# Motor-Driver.net
KiCad netlist of a schematic drawn in EAGLE
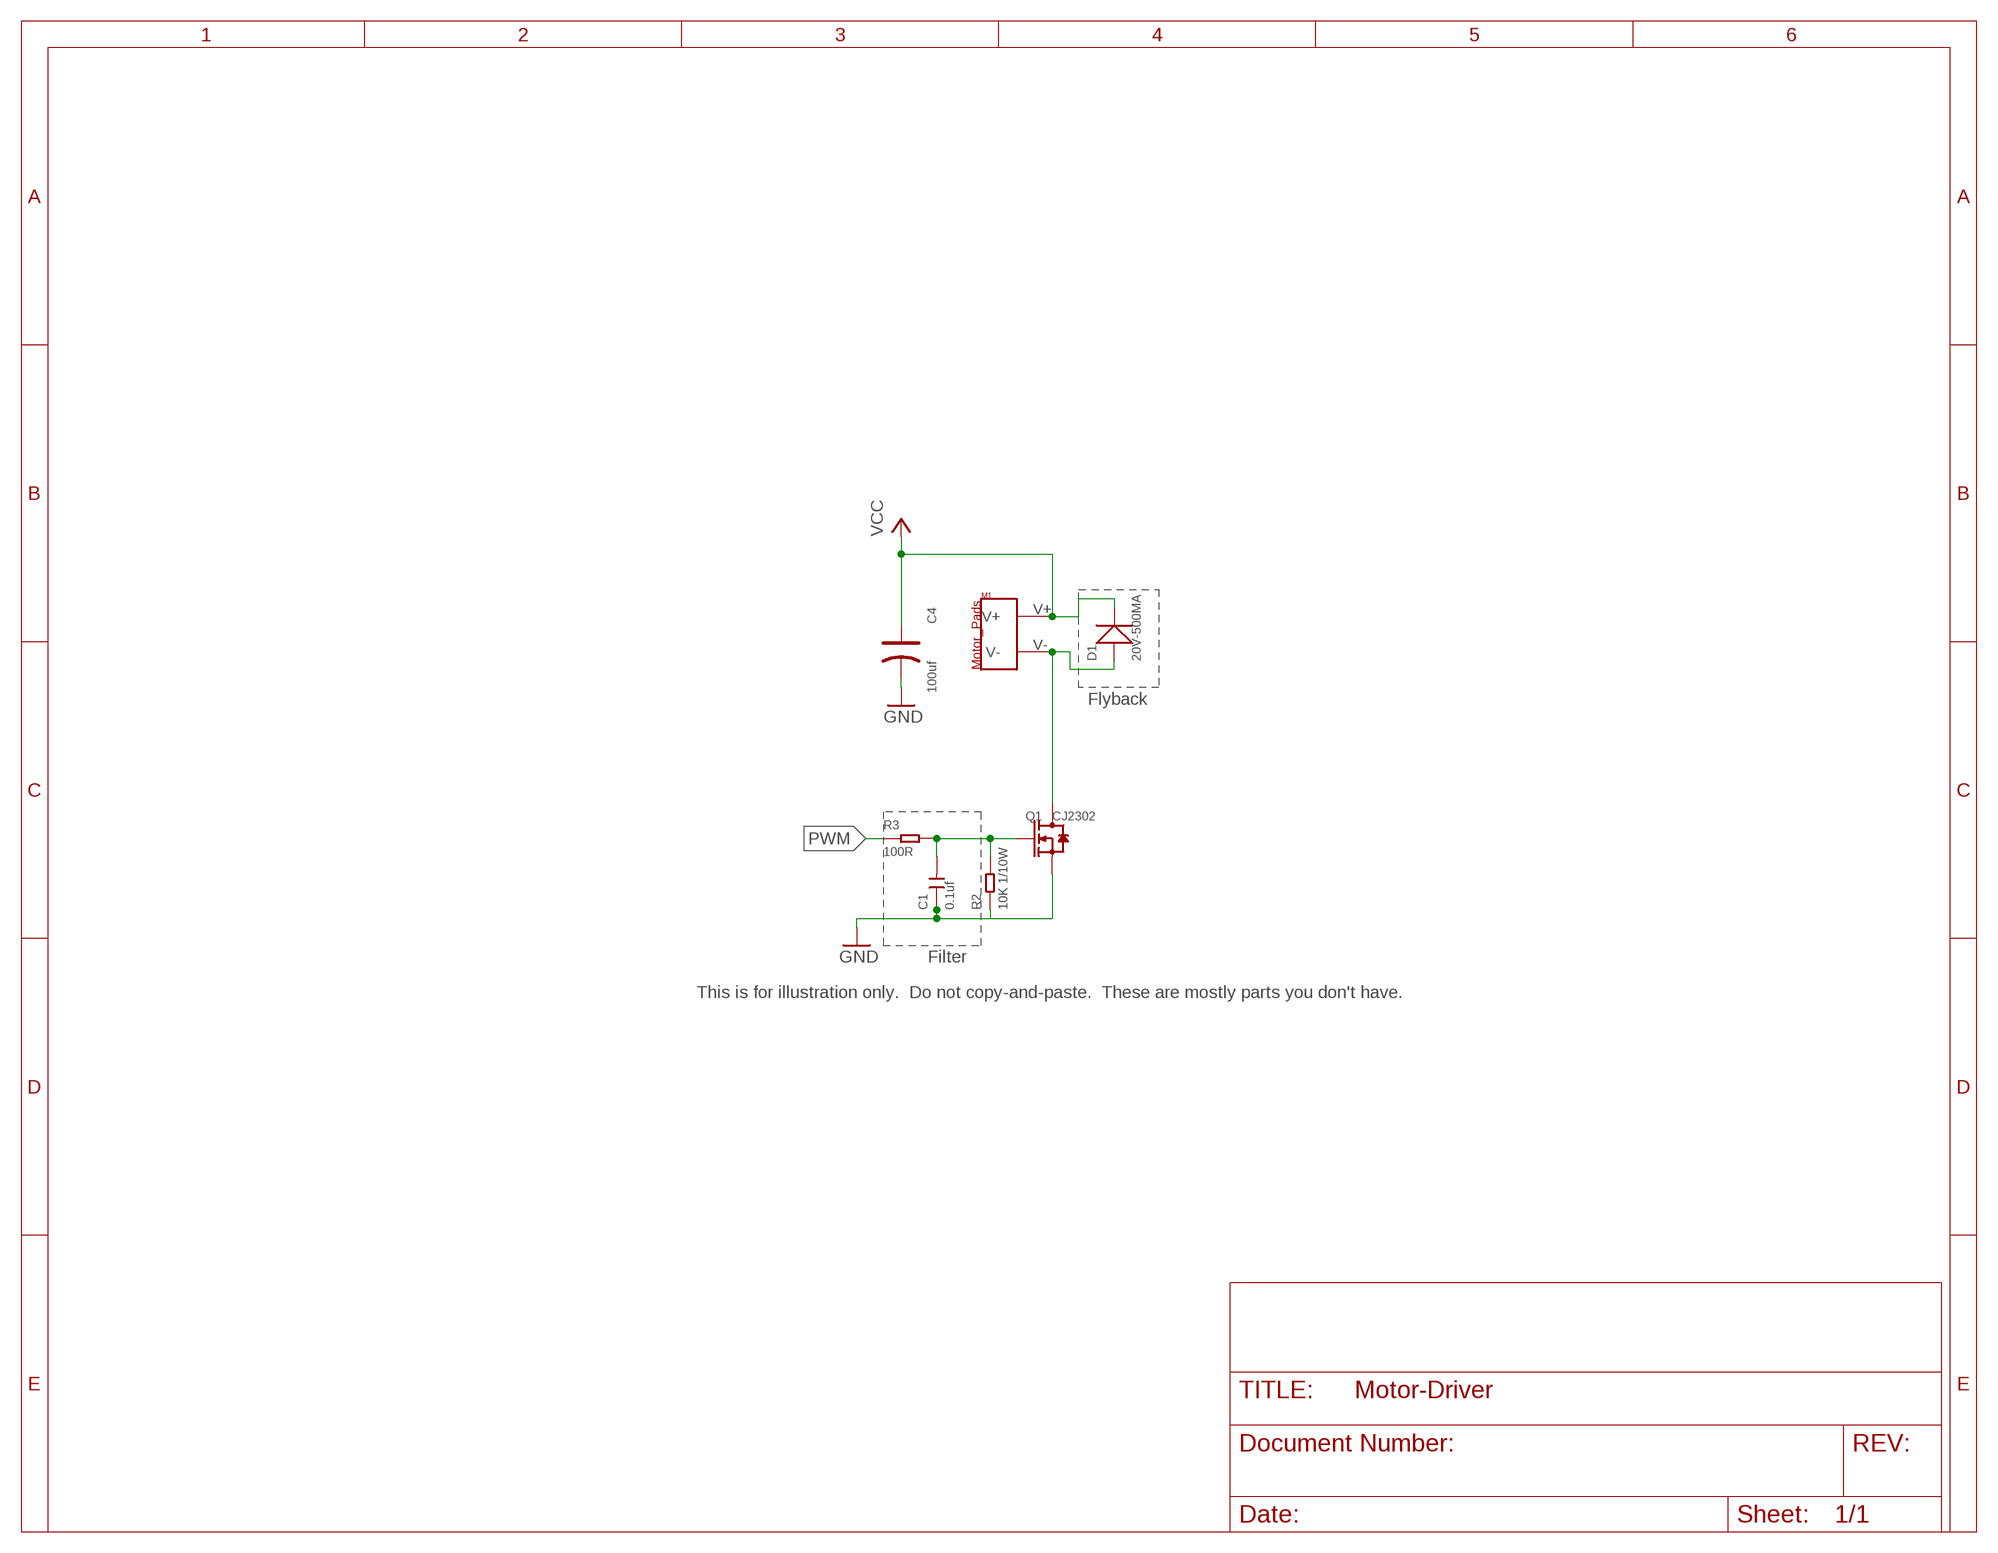
[diagram p0: schematic, sheet 1]

(export (version "E")
  (design (tool "Eeschema 10.0.6"))
  (components
    (comp (ref "C1")
      (value "0.1uf")
      (footprint "eagle-import:C0402")
      (fields (field (name "MPN") "CC0402KRX5R6BB105"))
      (libsource (lib "eagle-import") (part "CERAMIC-1UF-10V-10%-X5R(0402)"))
    )
    (comp (ref "C4")
      (value "100uf")
      (footprint "eagle-import:AVX-B")
      (fields (field (name "MPN") "TAJB107M010#NJ"))
      (libsource (lib "eagle-import") (part "TANTALUM-SMD-100UF-10V(AVX-B)"))
    )
    (comp (ref "D1")
      (value "20V-500MA")
      (footprint "eagle-import:SOD-123")
      (fields (field (name "MPN") "SS0520-7-F"))
      (libsource (lib "eagle-import") (part "SMD-DIODE-SCHOTTKY-20V-500MA(SOD-123)"))
    )
    (comp (ref "M1")
      (value "MOTOR_PADS")
      (footprint "eagle-import:MOTOR_PADS")
      (libsource (lib "eagle-import") (part "MOTOR_PADS"))
    )
    (comp (ref "Q1")
      (value "CJ2302")
      (footprint "eagle-import:SOT-23")
      (libsource (lib "eagle-import") (part "SMD-MOSFET-N-CH-20V-2.1A-CJ2302(SOT-23)"))
    )
    (comp (ref "R2")
      (value "10K 1/10W")
      (footprint "eagle-import:R0603")
      (fields (field (name "MPN") "RC0603JR-0710KL"))
      (libsource (lib "eagle-import") (part "SMD-RES-10K-5%-1/10W(0603)"))
    )
    (comp (ref "R3")
      (value "100R")
      (footprint "eagle-import:R0603")
      (fields (field (name "MPN") "RC0603JR-07100RL"))
      (libsource (lib "eagle-import") (part "SMD-RES-100R-5%-1/10W(0603)"))
    )
  )
  (nets
    (net (code "1") (name "GND") (class "Default")
      (node (ref "C1") (pin "1") (pinfunction "1_1") (pintype "passive"))
      (node (ref "C4") (pin "-") (pinfunction "-_-") (pintype "passive"))
      (node (ref "Q1") (pin "2") (pinfunction "S_2") (pintype "passive"))
      (node (ref "R2") (pin "1") (pinfunction "1_1") (pintype "passive"))
    )
    (net (code "2") (name "Net-(Q1-D)") (class "Default")
      (node (ref "D1") (pin "+") (pinfunction "+_+") (pintype "passive"))
      (node (ref "M1") (pin "V-") (pinfunction "V-_V-") (pintype "bidirectional"))
      (node (ref "Q1") (pin "3") (pinfunction "D_3") (pintype "passive"))
    )
    (net (code "3") (name "Net-(Q1-G)") (class "Default")
      (node (ref "C1") (pin "2") (pinfunction "2_2") (pintype "passive"))
      (node (ref "Q1") (pin "1") (pinfunction "G_1") (pintype "passive"))
      (node (ref "R2") (pin "2") (pinfunction "2_2") (pintype "passive"))
      (node (ref "R3") (pin "2") (pinfunction "2_2") (pintype "passive"))
    )
    (net (code "4") (name "PWM") (class "Default")
      (node (ref "R3") (pin "1") (pinfunction "1_1") (pintype "passive"))
    )
    (net (code "5") (name "VCC") (class "Default")
      (node (ref "C4") (pin "+") (pinfunction "+_+") (pintype "passive"))
      (node (ref "D1") (pin "-") (pinfunction "-_-") (pintype "passive"))
      (node (ref "M1") (pin "V+") (pinfunction "V+_V+") (pintype "bidirectional"))
    )
  )
)
